# main_2021-12-09.net
KiCad netlist of a schematic drawn in Altium Designer
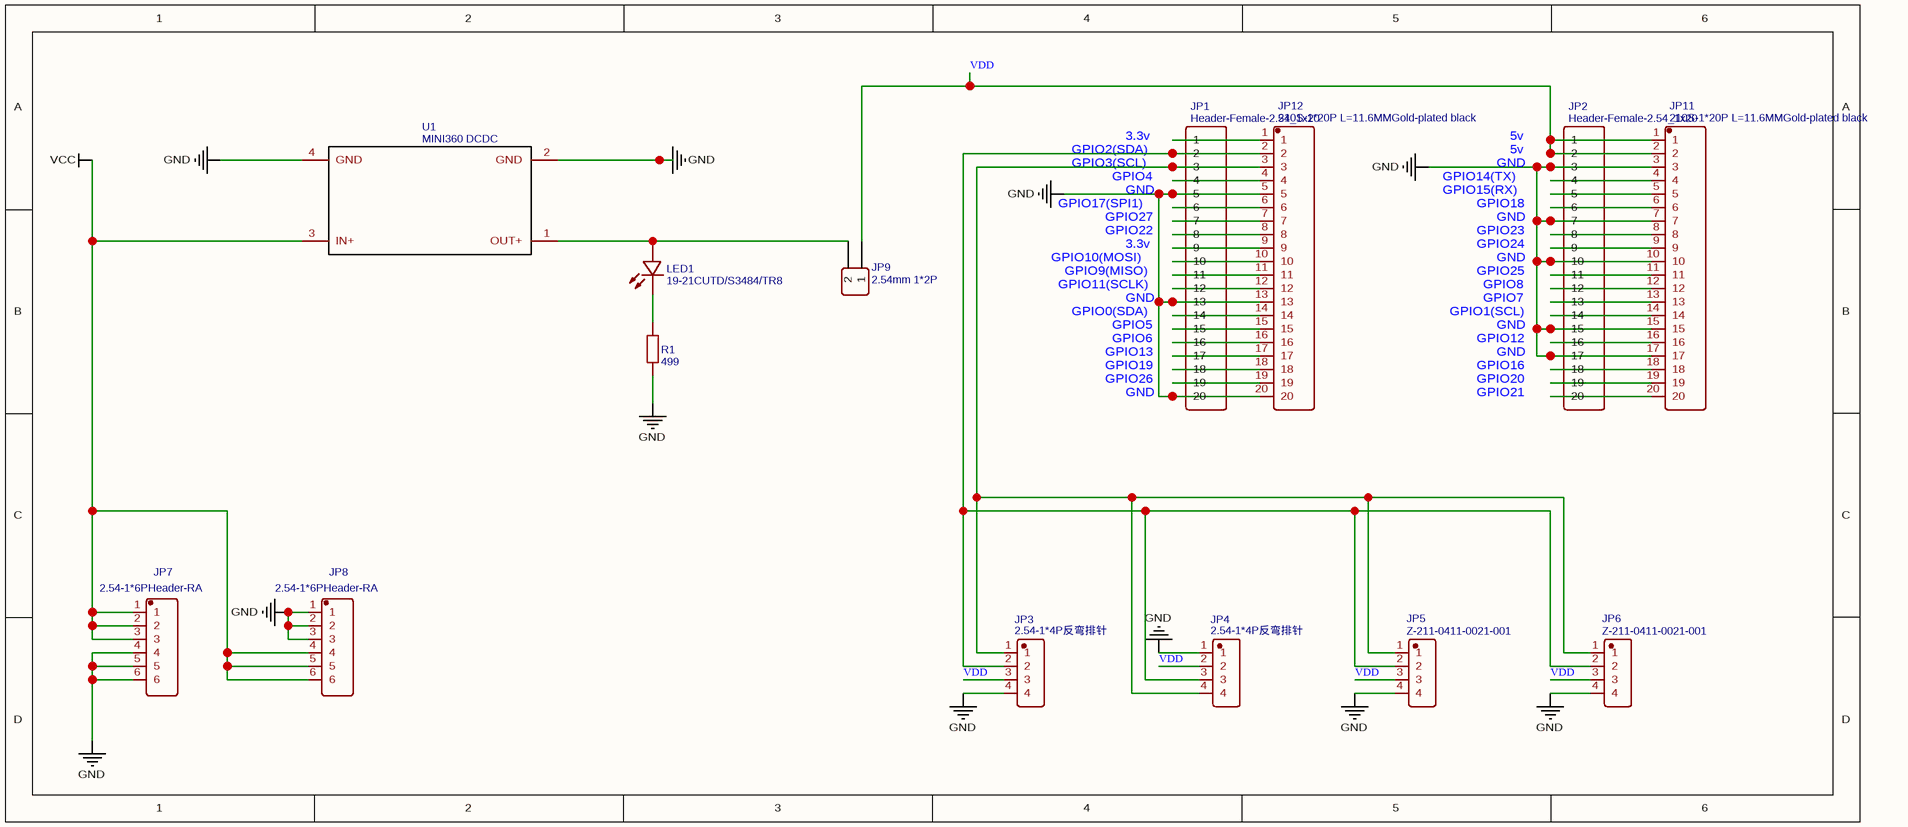
[diagram p0: main_2021-12-09.schdoc]

(export (version "E")
  (design (tool "Eeschema 10.0.6"))
  (components
    (comp (ref "JP1")
      (value "Header-Female-2.54_1x20")
      (fields
        (field (name "BOM_MANUFACTURER PART") "2.54mm 1*20P Female header")
        (field (name "BOM_SUPPLIER PART") "C50984")
      )
      (libsource (lib "altium-import") (part "root_0_Header-Female-2.54_1x20_"))
    )
    (comp (ref "JP2")
      (value "Header-Female-2.54_1x20")
      (fields
        (field (name "BOM_MANUFACTURER PART") "2.54mm 1*20P Female header")
        (field (name "BOM_SUPPLIER PART") "C50984")
      )
      (libsource (lib "altium-import") (part "root_0_Header-Female-2.54_1x20_"))
    )
    (comp (ref "JP3")
      (value "2.54-1*4P反弯排针")
      (fields (field (name "BOM_SUPPLIER PART") "C91552") (field (name "CONTRIBUTOR") "LCSC"))
      (libsource (lib "altium-import") (part "root_0_2.54-1*4P反弯排针_"))
    )
    (comp (ref "JP4")
      (value "2.54-1*4P反弯排针")
      (fields (field (name "BOM_SUPPLIER PART") "C91552") (field (name "CONTRIBUTOR") "LCSC"))
      (libsource (lib "altium-import") (part "root_0_2.54-1*4P反弯排针_"))
    )
    (comp (ref "JP5")
      (value "Z-211-0411-0021-001")
      (fields (field (name "BOM_SUPPLIER PART") "C152150") (field (name "CONTRIBUTOR") "LCSC"))
      (libsource (lib "altium-import") (part "root_0_Z-211-0411-0021-001_"))
    )
    (comp (ref "JP6")
      (value "Z-211-0411-0021-001")
      (fields (field (name "BOM_SUPPLIER PART") "C152150") (field (name "CONTRIBUTOR") "LCSC"))
      (libsource (lib "altium-import") (part "root_0_Z-211-0411-0021-001_"))
    )
    (comp (ref "JP7")
      (value "2.54-1*6PHeader-RA")
      (fields
        (field (name "BOM_MANUFACTURER PART") "2.54-1*6PHeader")
        (field (name "BOM_SUPPLIER PART") "C56816")
      )
      (libsource (lib "altium-import") (part "root_0_2.54-1*6PHeader-RA_"))
    )
    (comp (ref "JP8")
      (value "2.54-1*6PHeader-RA")
      (fields
        (field (name "BOM_MANUFACTURER PART") "2.54-1*6PHeader")
        (field (name "BOM_SUPPLIER PART") "C56816")
      )
      (libsource (lib "altium-import") (part "root_0_2.54-1*6PHeader-RA_"))
    )
    (comp (ref "JP9")
      (value "2.54mm 1*2P")
      (fields (field (name "BOM_SUPPLIER PART") "C36717"))
      (libsource (lib "altium-import") (part "root_3_2.54mm 1*2P_"))
    )
    (comp (ref "JP11")
      (value "210S-1*20P L=11.6MMGold-plated black")
      (fields (field (name "BOM_SUPPLIER PART") "C124374") (field (name "CONTRIBUTOR") "LCSC"))
      (libsource (lib "altium-import") (part "root_0_210S-1*20P L=11.6MMGold-plated black_"))
    )
    (comp (ref "JP12")
      (value "210S-1*20P L=11.6MMGold-plated black")
      (fields (field (name "BOM_SUPPLIER PART") "C124374") (field (name "CONTRIBUTOR") "LCSC"))
      (libsource (lib "altium-import") (part "root_0_210S-1*20P L=11.6MMGold-plated black_"))
    )
    (comp (ref "LED1")
      (value "19-21CUTD/S3484/TR8")
      (fields (field (name "BOM_SUPPLIER PART") "C264445") (field (name "CONTRIBUTOR") "LCSC"))
      (libsource (lib "altium-import") (part "root_1_19-21CUTD/S3484/TR8_"))
    )
    (comp (ref "R1")
      (value "499")
      (fields
        (field (name "BOM_SUPPLIER PART") "C209153")
        (field (name "BOM_MANUFACTURER PART") "RMS06FT4990")
        (field (name "CONTRIBUTOR") "LCSC")
      )
      (libsource (lib "altium-import") (part "root_1_499_"))
    )
    (comp (ref "U1")
      (value "MINI360 DCDC")
      (fields (field (name "CONTRIBUTOR") "libc0607"))
      (libsource (lib "altium-import") (part "root_2_MINI360 DCDC_"))
    )
  )
  (nets
    (net (code "1") (name "/VDD") (class "Default")
      (node (ref "JP11") (pin "1") (pinfunction "1_1") (pintype "passive"))
      (node (ref "JP11") (pin "2") (pinfunction "2_2") (pintype "passive"))
      (node (ref "JP2") (pin "1") (pinfunction "1_1") (pintype "passive"))
      (node (ref "JP2") (pin "2") (pinfunction "2_2") (pintype "passive"))
      (node (ref "JP3") (pin "3") (pinfunction "3_3") (pintype "passive"))
      (node (ref "JP4") (pin "2") (pinfunction "2_2") (pintype "passive"))
      (node (ref "JP5") (pin "3") (pinfunction "3_3") (pintype "passive"))
      (node (ref "JP6") (pin "3") (pinfunction "3_3") (pintype "passive"))
      (node (ref "JP9") (pin "1") (pinfunction "1_1") (pintype "passive"))
    )
    (net (code "2") (name "GND") (class "Default")
      (node (ref "JP1") (pin "13") (pinfunction "13_13") (pintype "passive"))
      (node (ref "JP1") (pin "20") (pinfunction "20_20") (pintype "passive"))
      (node (ref "JP1") (pin "5") (pinfunction "5_5") (pintype "passive"))
      (node (ref "JP11") (pin "10") (pinfunction "10_10") (pintype "passive"))
      (node (ref "JP11") (pin "15") (pinfunction "15_15") (pintype "passive"))
      (node (ref "JP11") (pin "17") (pinfunction "17_17") (pintype "passive"))
      (node (ref "JP11") (pin "3") (pinfunction "3_3") (pintype "passive"))
      (node (ref "JP11") (pin "7") (pinfunction "7_7") (pintype "passive"))
      (node (ref "JP12") (pin "13") (pinfunction "13_13") (pintype "passive"))
      (node (ref "JP12") (pin "20") (pinfunction "20_20") (pintype "passive"))
      (node (ref "JP12") (pin "5") (pinfunction "5_5") (pintype "passive"))
      (node (ref "JP2") (pin "10") (pinfunction "10_10") (pintype "passive"))
      (node (ref "JP2") (pin "15") (pinfunction "15_15") (pintype "passive"))
      (node (ref "JP2") (pin "17") (pinfunction "17_17") (pintype "passive"))
      (node (ref "JP2") (pin "3") (pinfunction "3_3") (pintype "passive"))
      (node (ref "JP2") (pin "7") (pinfunction "7_7") (pintype "passive"))
      (node (ref "JP3") (pin "4") (pinfunction "4_4") (pintype "passive"))
      (node (ref "JP4") (pin "1") (pinfunction "1_1") (pintype "passive"))
      (node (ref "JP5") (pin "4") (pinfunction "4_4") (pintype "passive"))
      (node (ref "JP6") (pin "4") (pinfunction "4_4") (pintype "passive"))
      (node (ref "JP7") (pin "4") (pinfunction "4_4") (pintype "passive"))
      (node (ref "JP7") (pin "5") (pinfunction "5_5") (pintype "passive"))
      (node (ref "JP7") (pin "6") (pinfunction "6_6") (pintype "passive"))
      (node (ref "JP8") (pin "1") (pinfunction "1_1") (pintype "passive"))
      (node (ref "JP8") (pin "2") (pinfunction "2_2") (pintype "passive"))
      (node (ref "JP8") (pin "3") (pinfunction "3_3") (pintype "passive"))
      (node (ref "R1") (pin "1") (pinfunction "1_1") (pintype "passive"))
      (node (ref "U1") (pin "2") (pinfunction "GND_2") (pintype "passive"))
      (node (ref "U1") (pin "4") (pinfunction "GND_4") (pintype "passive"))
    )
    (net (code "3") (name "Net-(JP1-Pad1)") (class "Default")
      (node (ref "JP1") (pin "1") (pinfunction "1_1") (pintype "passive"))
      (node (ref "JP12") (pin "1") (pinfunction "1_1") (pintype "passive"))
    )
    (net (code "4") (name "Net-(JP1-Pad2)") (class "Default")
      (node (ref "JP1") (pin "2") (pinfunction "2_2") (pintype "passive"))
      (node (ref "JP12") (pin "2") (pinfunction "2_2") (pintype "passive"))
      (node (ref "JP3") (pin "2") (pinfunction "2_2") (pintype "passive"))
      (node (ref "JP4") (pin "3") (pinfunction "3_3") (pintype "passive"))
      (node (ref "JP5") (pin "2") (pinfunction "2_2") (pintype "passive"))
      (node (ref "JP6") (pin "2") (pinfunction "2_2") (pintype "passive"))
    )
    (net (code "5") (name "Net-(JP1-Pad3)") (class "Default")
      (node (ref "JP1") (pin "3") (pinfunction "3_3") (pintype "passive"))
      (node (ref "JP12") (pin "3") (pinfunction "3_3") (pintype "passive"))
      (node (ref "JP3") (pin "1") (pinfunction "1_1") (pintype "passive"))
      (node (ref "JP4") (pin "4") (pinfunction "4_4") (pintype "passive"))
      (node (ref "JP5") (pin "1") (pinfunction "1_1") (pintype "passive"))
      (node (ref "JP6") (pin "1") (pinfunction "1_1") (pintype "passive"))
    )
    (net (code "6") (name "Net-(JP1-Pad4)") (class "Default")
      (node (ref "JP1") (pin "4") (pinfunction "4_4") (pintype "passive"))
      (node (ref "JP12") (pin "4") (pinfunction "4_4") (pintype "passive"))
    )
    (net (code "7") (name "Net-(JP1-Pad6)") (class "Default")
      (node (ref "JP1") (pin "6") (pinfunction "6_6") (pintype "passive"))
      (node (ref "JP12") (pin "6") (pinfunction "6_6") (pintype "passive"))
    )
    (net (code "8") (name "Net-(JP1-Pad7)") (class "Default")
      (node (ref "JP1") (pin "7") (pinfunction "7_7") (pintype "passive"))
      (node (ref "JP12") (pin "7") (pinfunction "7_7") (pintype "passive"))
    )
    (net (code "9") (name "Net-(JP1-Pad8)") (class "Default")
      (node (ref "JP1") (pin "8") (pinfunction "8_8") (pintype "passive"))
      (node (ref "JP12") (pin "8") (pinfunction "8_8") (pintype "passive"))
    )
    (net (code "10") (name "Net-(JP1-Pad9)") (class "Default")
      (node (ref "JP1") (pin "9") (pinfunction "9_9") (pintype "passive"))
      (node (ref "JP12") (pin "9") (pinfunction "9_9") (pintype "passive"))
    )
    (net (code "11") (name "Net-(JP1-Pad10)") (class "Default")
      (node (ref "JP1") (pin "10") (pinfunction "10_10") (pintype "passive"))
      (node (ref "JP12") (pin "10") (pinfunction "10_10") (pintype "passive"))
    )
    (net (code "12") (name "Net-(JP1-Pad11)") (class "Default")
      (node (ref "JP1") (pin "11") (pinfunction "11_11") (pintype "passive"))
      (node (ref "JP12") (pin "11") (pinfunction "11_11") (pintype "passive"))
    )
    (net (code "13") (name "Net-(JP1-Pad12)") (class "Default")
      (node (ref "JP1") (pin "12") (pinfunction "12_12") (pintype "passive"))
      (node (ref "JP12") (pin "12") (pinfunction "12_12") (pintype "passive"))
    )
    (net (code "14") (name "Net-(JP1-Pad14)") (class "Default")
      (node (ref "JP1") (pin "14") (pinfunction "14_14") (pintype "passive"))
      (node (ref "JP12") (pin "14") (pinfunction "14_14") (pintype "passive"))
    )
    (net (code "15") (name "Net-(JP1-Pad15)") (class "Default")
      (node (ref "JP1") (pin "15") (pinfunction "15_15") (pintype "passive"))
      (node (ref "JP12") (pin "15") (pinfunction "15_15") (pintype "passive"))
    )
    (net (code "16") (name "Net-(JP1-Pad16)") (class "Default")
      (node (ref "JP1") (pin "16") (pinfunction "16_16") (pintype "passive"))
      (node (ref "JP12") (pin "16") (pinfunction "16_16") (pintype "passive"))
    )
    (net (code "17") (name "Net-(JP1-Pad17)") (class "Default")
      (node (ref "JP1") (pin "17") (pinfunction "17_17") (pintype "passive"))
      (node (ref "JP12") (pin "17") (pinfunction "17_17") (pintype "passive"))
    )
    (net (code "18") (name "Net-(JP1-Pad18)") (class "Default")
      (node (ref "JP1") (pin "18") (pinfunction "18_18") (pintype "passive"))
      (node (ref "JP12") (pin "18") (pinfunction "18_18") (pintype "passive"))
    )
    (net (code "19") (name "Net-(JP1-Pad19)") (class "Default")
      (node (ref "JP1") (pin "19") (pinfunction "19_19") (pintype "passive"))
      (node (ref "JP12") (pin "19") (pinfunction "19_19") (pintype "passive"))
    )
    (net (code "20") (name "Net-(JP11-Pad4)") (class "Default")
      (node (ref "JP11") (pin "4") (pinfunction "4_4") (pintype "passive"))
      (node (ref "JP2") (pin "4") (pinfunction "4_4") (pintype "passive"))
    )
    (net (code "21") (name "Net-(JP11-Pad5)") (class "Default")
      (node (ref "JP11") (pin "5") (pinfunction "5_5") (pintype "passive"))
      (node (ref "JP2") (pin "5") (pinfunction "5_5") (pintype "passive"))
    )
    (net (code "22") (name "Net-(JP11-Pad6)") (class "Default")
      (node (ref "JP11") (pin "6") (pinfunction "6_6") (pintype "passive"))
      (node (ref "JP2") (pin "6") (pinfunction "6_6") (pintype "passive"))
    )
    (net (code "23") (name "Net-(JP11-Pad8)") (class "Default")
      (node (ref "JP11") (pin "8") (pinfunction "8_8") (pintype "passive"))
      (node (ref "JP2") (pin "8") (pinfunction "8_8") (pintype "passive"))
    )
    (net (code "24") (name "Net-(JP11-Pad9)") (class "Default")
      (node (ref "JP11") (pin "9") (pinfunction "9_9") (pintype "passive"))
      (node (ref "JP2") (pin "9") (pinfunction "9_9") (pintype "passive"))
    )
    (net (code "25") (name "Net-(JP11-Pad11)") (class "Default")
      (node (ref "JP11") (pin "11") (pinfunction "11_11") (pintype "passive"))
      (node (ref "JP2") (pin "11") (pinfunction "11_11") (pintype "passive"))
    )
    (net (code "26") (name "Net-(JP11-Pad12)") (class "Default")
      (node (ref "JP11") (pin "12") (pinfunction "12_12") (pintype "passive"))
      (node (ref "JP2") (pin "12") (pinfunction "12_12") (pintype "passive"))
    )
    (net (code "27") (name "Net-(JP11-Pad13)") (class "Default")
      (node (ref "JP11") (pin "13") (pinfunction "13_13") (pintype "passive"))
      (node (ref "JP2") (pin "13") (pinfunction "13_13") (pintype "passive"))
    )
    (net (code "28") (name "Net-(JP11-Pad14)") (class "Default")
      (node (ref "JP11") (pin "14") (pinfunction "14_14") (pintype "passive"))
      (node (ref "JP2") (pin "14") (pinfunction "14_14") (pintype "passive"))
    )
    (net (code "29") (name "Net-(JP11-Pad16)") (class "Default")
      (node (ref "JP11") (pin "16") (pinfunction "16_16") (pintype "passive"))
      (node (ref "JP2") (pin "16") (pinfunction "16_16") (pintype "passive"))
    )
    (net (code "30") (name "Net-(JP11-Pad18)") (class "Default")
      (node (ref "JP11") (pin "18") (pinfunction "18_18") (pintype "passive"))
      (node (ref "JP2") (pin "18") (pinfunction "18_18") (pintype "passive"))
    )
    (net (code "31") (name "Net-(JP11-Pad19)") (class "Default")
      (node (ref "JP11") (pin "19") (pinfunction "19_19") (pintype "passive"))
      (node (ref "JP2") (pin "19") (pinfunction "19_19") (pintype "passive"))
    )
    (net (code "32") (name "Net-(JP11-Pad20)") (class "Default")
      (node (ref "JP11") (pin "20") (pinfunction "20_20") (pintype "passive"))
      (node (ref "JP2") (pin "20") (pinfunction "20_20") (pintype "passive"))
    )
    (net (code "33") (name "Net-(LED1-A)") (class "Default")
      (node (ref "JP9") (pin "2") (pinfunction "2_2") (pintype "passive"))
      (node (ref "LED1") (pin "1") (pinfunction "A_1") (pintype "passive"))
      (node (ref "U1") (pin "1") (pinfunction "OUT+_1") (pintype "passive"))
    )
    (net (code "34") (name "Net-(LED1-K)") (class "Default")
      (node (ref "LED1") (pin "2") (pinfunction "K_2") (pintype "passive"))
      (node (ref "R1") (pin "2") (pinfunction "2_2") (pintype "passive"))
    )
    (net (code "35") (name "VCC") (class "Default")
      (node (ref "JP7") (pin "1") (pinfunction "1_1") (pintype "passive"))
      (node (ref "JP7") (pin "2") (pinfunction "2_2") (pintype "passive"))
      (node (ref "JP7") (pin "3") (pinfunction "3_3") (pintype "passive"))
      (node (ref "JP8") (pin "4") (pinfunction "4_4") (pintype "passive"))
      (node (ref "JP8") (pin "5") (pinfunction "5_5") (pintype "passive"))
      (node (ref "JP8") (pin "6") (pinfunction "6_6") (pintype "passive"))
      (node (ref "U1") (pin "3") (pinfunction "IN+_3") (pintype "passive"))
    )
  )
)
